# JacdacG0Button_40.net
KiCad netlist of a schematic drawn in Altium Designer
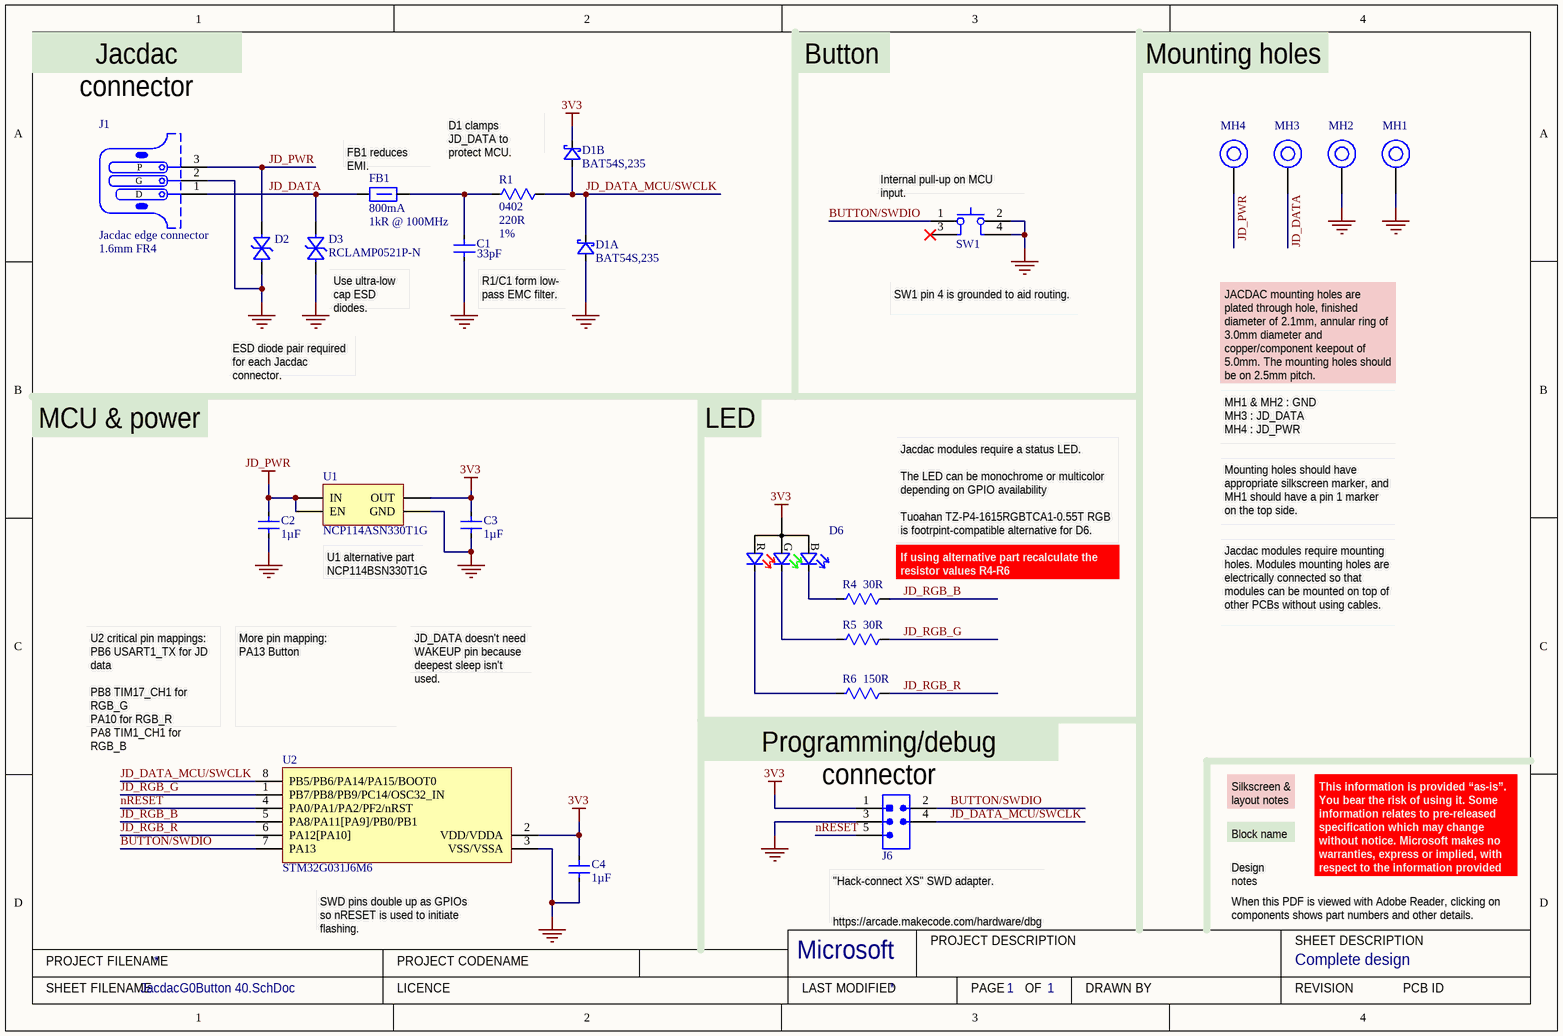
[diagram p0: JacdacG0Button 40.SchDoc]

(export (version "E")
  (design (tool "Eeschema 10.0.6"))
  (components
    (comp (ref "C1")
      (value "CL05C330JB5NNNC")
      (footprint "C0402_0.55MM - without outline")
      (description "CAP CER 33PF 50V C0G/NP0 0402")
      (fields
        (field (name "MANUFACTURER") "Samsung")
        (field (name "TOLERANCE") "5%")
        (field (name "CAPACITANCE") "33pF")
      )
      (libsource (lib "Samsung") (part "CL05C330JB5NNNC"))
    )
    (comp (ref "C2")
      (value "CL05A105KP5NNNC")
      (footprint "C0402_0.55MM - without outline")
      (description "CAP CER 1UF 10V X5R 0402")
      (fields
        (field (name "MANUFACTURER") "Samsung")
        (field (name "TOLERANCE") "10%")
        (field (name "CAPACITANCE") "1µF")
        (field (name "CREATED") "DG")
        (field (name "CHECKED") "?")
      )
      (libsource (lib "Samsung") (part "CL05A105KP5NNNC"))
    )
    (comp (ref "C3")
      (value "CL05A105KP5NNNC")
      (footprint "C0402_0.55MM - without outline")
      (description "CAP CER 1UF 10V X5R 0402")
      (fields
        (field (name "MANUFACTURER") "Samsung")
        (field (name "TOLERANCE") "10%")
        (field (name "CAPACITANCE") "1µF")
        (field (name "CREATED") "DG")
        (field (name "CHECKED") "?")
      )
      (libsource (lib "Samsung") (part "CL05A105KP5NNNC"))
    )
    (comp (ref "C4")
      (value "CL05A105KP5NNNC")
      (footprint "C0402_0.55MM - without outline")
      (description "CAP CER 1UF 10V X5R 0402")
      (fields
        (field (name "MANUFACTURER") "Samsung")
        (field (name "TOLERANCE") "10%")
        (field (name "CAPACITANCE") "1µF")
        (field (name "CREATED") "DG")
        (field (name "CHECKED") "?")
      )
      (libsource (lib "Samsung") (part "CL05A105KP5NNNC"))
    )
    (comp (ref "D1")
      (value "BAT54S")
      (footprint "NXP-BAT54S-TO-236AB - without outline")
      (description "DIODE ARRAY SCHOTTKY 30V SOT23")
      (fields (field (name "MANUFACTURER") "Nexperia") (field (name "MANUFACTURER PART NUMBER") "BAT54S,235"))
      (libsource (lib "NXP") (part "BAT54S"))
    )
    (comp (ref "D2")
      (value "RCLAMP0521P-N")
      (footprint "TVS 0402 - without outline")
      (description "Bidirectional 5V (Max) 6V 16V 3.5A (8/20us) 0402 TVS RoHS")
      (fields
        (field (name "MANUFACTURER") "Born Semiconductor")
        (field (name "CREATED BY") "D Gakure")
        (field (name "CHECKED BY") "?")
      )
      (libsource (lib "BornSemiconductor") (part "RCLAMP0521P-N"))
    )
    (comp (ref "D3")
      (value "RCLAMP0521P-N")
      (footprint "TVS 0402 - without outline")
      (description "Bidirectional 5V (Max) 6V 16V 3.5A (8/20us) 0402 TVS RoHS")
      (fields
        (field (name "MANUFACTURER") "Born Semiconductor")
        (field (name "MANUFACTURER PART NUMBER") "RCLAMP0521P-N")
        (field (name "CREATED BY") "D Gakure")
        (field (name "CHECKED BY") "?")
      )
      (libsource (lib "BornSemiconductor") (part "RCLAMP0521P-N"))
    )
    (comp (ref "D6")
      (value "TZ-P4-1615RGBTCA1-0.55T")
      (footprint "TZ-P4-1615RGBTCA1-0.55T")
      (description "1615 Light Emitting Diodes (LED) RoHS")
      (fields
        (field (name "MANUFACTURER") "TUOZHAN")
        (field (name "CREATED BY") "D. Gakure")
        (field (name "CHECKED BY") "?")
      )
      (libsource (lib "Tuozhan") (part "TZ-P4-1615RGBTCA1-0.55T"))
    )
    (comp (ref "FB1")
      (value "TDK MPZ1608S102ATA00")
      (footprint "TDK MPZ1608 0.8mm - without outline")
      (description "0603 1k@100MHz 0.8A chip")
      (fields
        (field (name "TOLERANCE") "25%")
        (field (name "MANUFACTURER") "TDK")
        (field (name "CURRENT RATING") "800mA")
        (field (name "IMPEDANCE") "1kR @ 100MHz")
      )
      (libsource (lib "TDK") (part "TDK MPZ1608S102ATA00"))
    )
    (comp (ref "J1")
      (value "Jacdac edge connector")
      (footprint "JACDAC_EDGE_CONNECTOR_0.2mm_T&G")
      (description "3 pin Jacdac edge connector 1.27mm pitch")
      (fields
        (field (name "MANUFACTURER PART NUMBER") "JACDAC_EDGE_CONNECTOR")
        (field (name "PCB TYPE") "1.6mm FR4")
        (field (name "CHECKED BY") "?")
        (field (name "CREATED BY") "D. Gakure")
      )
      (libsource (lib "generic-con") (part "Jacdac edge connector"))
    )
    (comp (ref "J6")
      (value "Hack Connect Mini 1.27 mm pitch 2-row")
      (footprint "HACK_CONNECT_MINI_5_X_1_27")
      (libsource (lib "HackConnect") (part "HACK_CONNECT_MINI"))
    )
    (comp (ref "MH1")
      (value "MH_5.0MMK_3.0MMC_2.1MMD_PTH")
      (footprint "MH_5.0MMK_3.0MMC_2.1MMD_PTH")
      (description "Mounting Hole 5.0mm keepout, 3.0mm annualar ring and 2.1mm Drill PTH")
      (libsource (lib "generic") (part "MH_5.0MMK_3.0MMC_2.1MMD_PTH"))
    )
    (comp (ref "MH2")
      (value "MH_5.0MMK_3.0MMC_2.1MMD_PTH")
      (footprint "MH_5.0MMK_3.0MMC_2.1MMD_PTH")
      (description "Mounting Hole 5.0mm keepout, 3.0mm annualar ring and 2.1mm Drill PTH")
      (libsource (lib "generic") (part "MH_5.0MMK_3.0MMC_2.1MMD_PTH"))
    )
    (comp (ref "MH3")
      (value "MH_5.0MMK_3.0MMC_2.1MMD_PTH")
      (footprint "MH_5.0MMK_3.0MMC_2.1MMD_PTH")
      (description "Mounting Hole 5.0mm keepout, 3.0mm annualar ring and 2.1mm Drill PTH")
      (libsource (lib "generic") (part "MH_5.0MMK_3.0MMC_2.1MMD_PTH"))
    )
    (comp (ref "MH4")
      (value "MH_5.0MMK_3.0MMC_2.1MMD_PTH")
      (footprint "MH_5.0MMK_3.0MMC_2.1MMD_PTH")
      (description "Mounting Hole 5.0mm keepout, 3.0mm annualar ring and 2.1mm Drill PTH")
      (libsource (lib "generic") (part "MH_5.0MMK_3.0MMC_2.1MMD_PTH"))
    )
    (comp (ref "R1")
      (value "RC0402FR-07220RL")
      (footprint "R0402 - Without outline")
      (description "RES SMD 220 OHM 1% 1/16W 0402")
      (fields
        (field (name "MANUFACTURER") "Yageo")
        (field (name "CASE CODE (IMPERIAL)") "0402")
        (field (name "RESISTANCE") "220R")
        (field (name "TOLERANCE") "1%")
        (field (name "CREATED") "D.G")
        (field (name "CHECKED") "?")
      )
      (libsource (lib "Yageo") (part "RC0402FR-07220RL"))
    )
    (comp (ref "R4")
      (value "RC0402FR-0730RL")
      (footprint "R0402 - Without outline")
      (description "RES SMD 30 OHM 1% 1/16W 0402")
      (fields
        (field (name "MANUFACTURER") "Yageo")
        (field (name "RESISTANCE") "30R")
        (field (name "TOLERANCE") "1%")
        (field (name "CREATED BY") "D. Gakure")
        (field (name "CHECKED BY") "?")
      )
      (libsource (lib "Yageo") (part "RC0402FR-0730RL"))
    )
    (comp (ref "R5")
      (value "RC0402FR-0730RL")
      (footprint "R0402 - Without outline")
      (description "RES SMD 30 OHM 1% 1/16W 0402")
      (fields
        (field (name "MANUFACTURER") "Yageo")
        (field (name "RESISTANCE") "30R")
        (field (name "TOLERANCE") "1%")
        (field (name "CREATED BY") "D. Gakure")
        (field (name "CHECKED BY") "?")
      )
      (libsource (lib "Yageo") (part "RC0402FR-0730RL"))
    )
    (comp (ref "R6")
      (value "RC0402FR-07150RL")
      (footprint "R0402 - Without outline")
      (description "RES SMD 150 OHM 1% 1/16W 0402")
      (fields
        (field (name "MANUFACTURER") "Yageo")
        (field (name "RESISTANCE") "150R")
        (field (name "TOLERANCE") "1%")
        (field (name "CREATED BY") "D. Gakure")
        (field (name "CHECKED BY") "?")
      )
      (libsource (lib "Yageo") (part "RC0402FR-07150RL"))
    )
    (comp (ref "SW1")
      (value "Tact Wurth 430152050826")
      (footprint "Wurth 430152050836 - medium")
      (description "6x6mm SPST 0.05A 12VDC SMD 260gf")
      (fields
        (field (name "MANUFACTURER") "Wurth Electronics")
        (field (name "MANUFACTURER PART NUMBER") "430152050826")
      )
      (libsource (lib "Wurth") (part "Tact Wurth 430152050826"))
    )
    (comp (ref "U1")
      (value "LDO 3.3V/300 mA")
      (footprint "ON_SEMI-SOT23-5 - without outline")
      (fields
        (field (name "MANUFACTURER") "ON Semiconductor")
        (field (name "MANUFACTURER PART NUMBER") "NCP114ASN330T1G")
        (field (name "CREATED") "DG")
        (field (name "CHECKED") "?")
      )
      (libsource (lib "OnSemiconductor") (part "NCP114ASN330T1G"))
    )
    (comp (ref "U2")
      (value "STM32G031J6M6")
      (footprint "8-SOIC")
      (description "MCU 32-bit ARM Cortex M0+ RISC 32KB Flash 2.5V/3.3V 8-Pin SO N Tube")
      (fields
        (field (name "MANUFACTURER") "STMicroelectronics")
        (field (name "MANUFACTURER PART NUMBER") "STM32G031J6M6")
        (field (name "CREATED BY") "D. Gakure")
        (field (name "CHECKED BY") "?")
      )
      (libsource (lib "ST") (part "STM32G031J6M6"))
    )
  )
  (nets
    (net (code "1") (name "/BUTTON{slash}SWDIO") (class "Default")
      (node (ref "J6") (pin "2") (pinfunction "SWDIO_2") (pintype "passive"))
      (node (ref "SW1") (pin "1") (pinfunction "1_1") (pintype "passive"))
      (node (ref "U2") (pin "7") (pinfunction "PA13_7") (pintype "passive"))
    )
    (net (code "2") (name "/JD_DATA") (class "Default")
      (node (ref "D3") (pin "1") (pinfunction "K_1") (pintype "passive"))
      (node (ref "FB1") (pin "1") (pinfunction "1_1") (pintype "passive"))
      (node (ref "J1") (pin "1") (pinfunction "D_1") (pintype "passive"))
      (node (ref "MH3") (pin "1") (pinfunction "1_1") (pintype "passive"))
    )
    (net (code "3") (name "/JD_DATA_MCU{slash}SWCLK") (class "Default")
      (node (ref "D1") (pin "3") (pinfunction "K_3") (pintype "passive"))
      (node (ref "J6") (pin "4") (pinfunction "SWCLK_4") (pintype "passive"))
      (node (ref "R1") (pin "1") (pinfunction "1_1") (pintype "passive"))
      (node (ref "U2") (pin "8") (pinfunction "PB5/PB6/PA14/PA15/BOOT0_8") (pintype "passive"))
    )
    (net (code "4") (name "/JD_RGB_B") (class "Default")
      (node (ref "R4") (pin "2") (pinfunction "2_2") (pintype "passive"))
      (node (ref "U2") (pin "5") (pinfunction "PA8/PA11[PA9]/PB0/PB1_5") (pintype "passive"))
    )
    (net (code "5") (name "/JD_RGB_G") (class "Default")
      (node (ref "R5") (pin "2") (pinfunction "2_2") (pintype "passive"))
      (node (ref "U2") (pin "1") (pinfunction "PB7/PB8/PB9/PC14/OSC32_IN_1") (pintype "passive"))
    )
    (net (code "6") (name "/JD_RGB_R") (class "Default")
      (node (ref "R6") (pin "2") (pinfunction "2_2") (pintype "passive"))
      (node (ref "U2") (pin "6") (pinfunction "PA12[PA10]_6") (pintype "passive"))
    )
    (net (code "7") (name "/nRESET") (class "Default")
      (node (ref "J6") (pin "5") (pinfunction "RESET_5") (pintype "passive"))
      (node (ref "U2") (pin "4") (pinfunction "PA0/PA1/PA2/PF2/nRST_4") (pintype "passive"))
    )
    (net (code "8") (name "3V3") (class "Default")
      (node (ref "C3") (pin "2") (pinfunction "2_2") (pintype "passive"))
      (node (ref "C4") (pin "2") (pinfunction "2_2") (pintype "passive"))
      (node (ref "D1") (pin "2") (pinfunction "K_2") (pintype "passive"))
      (node (ref "D6") (pin "1") (pinfunction "A_1") (pintype "passive"))
      (node (ref "J6") (pin "1") (pinfunction "VCC_1") (pintype "passive"))
      (node (ref "U1") (pin "5") (pinfunction "OUT_5") (pintype "passive"))
      (node (ref "U2") (pin "2") (pinfunction "VDD/VDDA_2") (pintype "passive"))
    )
    (net (code "9") (name "GND") (class "Default")
      (node (ref "C1") (pin "1") (pinfunction "1_1") (pintype "passive"))
      (node (ref "C2") (pin "1") (pinfunction "1_1") (pintype "passive"))
      (node (ref "C3") (pin "1") (pinfunction "1_1") (pintype "passive"))
      (node (ref "C4") (pin "1") (pinfunction "1_1") (pintype "passive"))
      (node (ref "D1") (pin "1") (pinfunction "A_1") (pintype "passive"))
      (node (ref "D2") (pin "2") (pinfunction "A_2") (pintype "passive"))
      (node (ref "D3") (pin "2") (pinfunction "A_2") (pintype "passive"))
      (node (ref "J1") (pin "2") (pinfunction "G_2") (pintype "passive"))
      (node (ref "J6") (pin "3") (pinfunction "GND_3") (pintype "passive"))
      (node (ref "MH1") (pin "1") (pinfunction "1_1") (pintype "passive"))
      (node (ref "MH2") (pin "1") (pinfunction "1_1") (pintype "passive"))
      (node (ref "SW1") (pin "2") (pinfunction "2_2") (pintype "passive"))
      (node (ref "SW1") (pin "4") (pinfunction "4_4") (pintype "passive"))
      (node (ref "U1") (pin "2") (pinfunction "GND_2") (pintype "passive"))
      (node (ref "U2") (pin "3") (pinfunction "VSS/VSSA_3") (pintype "passive"))
    )
    (net (code "10") (name "JD_PWR") (class "Default")
      (node (ref "C2") (pin "2") (pinfunction "2_2") (pintype "passive"))
      (node (ref "D2") (pin "1") (pinfunction "K_1") (pintype "passive"))
      (node (ref "J1") (pin "3") (pinfunction "P_3") (pintype "passive"))
      (node (ref "MH4") (pin "1") (pinfunction "1_1") (pintype "passive"))
      (node (ref "U1") (pin "1") (pinfunction "IN_1") (pintype "passive"))
      (node (ref "U1") (pin "3") (pinfunction "EN_3") (pintype "passive"))
    )
    (net (code "11") (name "Net-(C1-Pad2)") (class "Default")
      (node (ref "C1") (pin "2") (pinfunction "2_2") (pintype "passive"))
      (node (ref "FB1") (pin "2") (pinfunction "2_2") (pintype "passive"))
      (node (ref "R1") (pin "2") (pinfunction "2_2") (pintype "passive"))
    )
    (net (code "12") (name "Net-(D6-B)") (class "Default")
      (node (ref "D6") (pin "4") (pinfunction "B_4") (pintype "passive"))
      (node (ref "R4") (pin "1") (pinfunction "1_1") (pintype "passive"))
    )
    (net (code "13") (name "Net-(D6-G)") (class "Default")
      (node (ref "D6") (pin "3") (pinfunction "G_3") (pintype "passive"))
      (node (ref "R5") (pin "1") (pinfunction "1_1") (pintype "passive"))
    )
    (net (code "14") (name "Net-(D6-R)") (class "Default")
      (node (ref "D6") (pin "2") (pinfunction "R_2") (pintype "passive"))
      (node (ref "R6") (pin "1") (pinfunction "1_1") (pintype "passive"))
    )
    (net (code "15") (name "unconnected-(SW1-Pad3)") (class "Default")
      (node (ref "SW1") (pin "3") (pinfunction "3_3") (pintype "passive+no_connect"))
    )
  )
)
